# BatteryCharge.net
KiCad netlist of a schematic drawn in Altium Designer
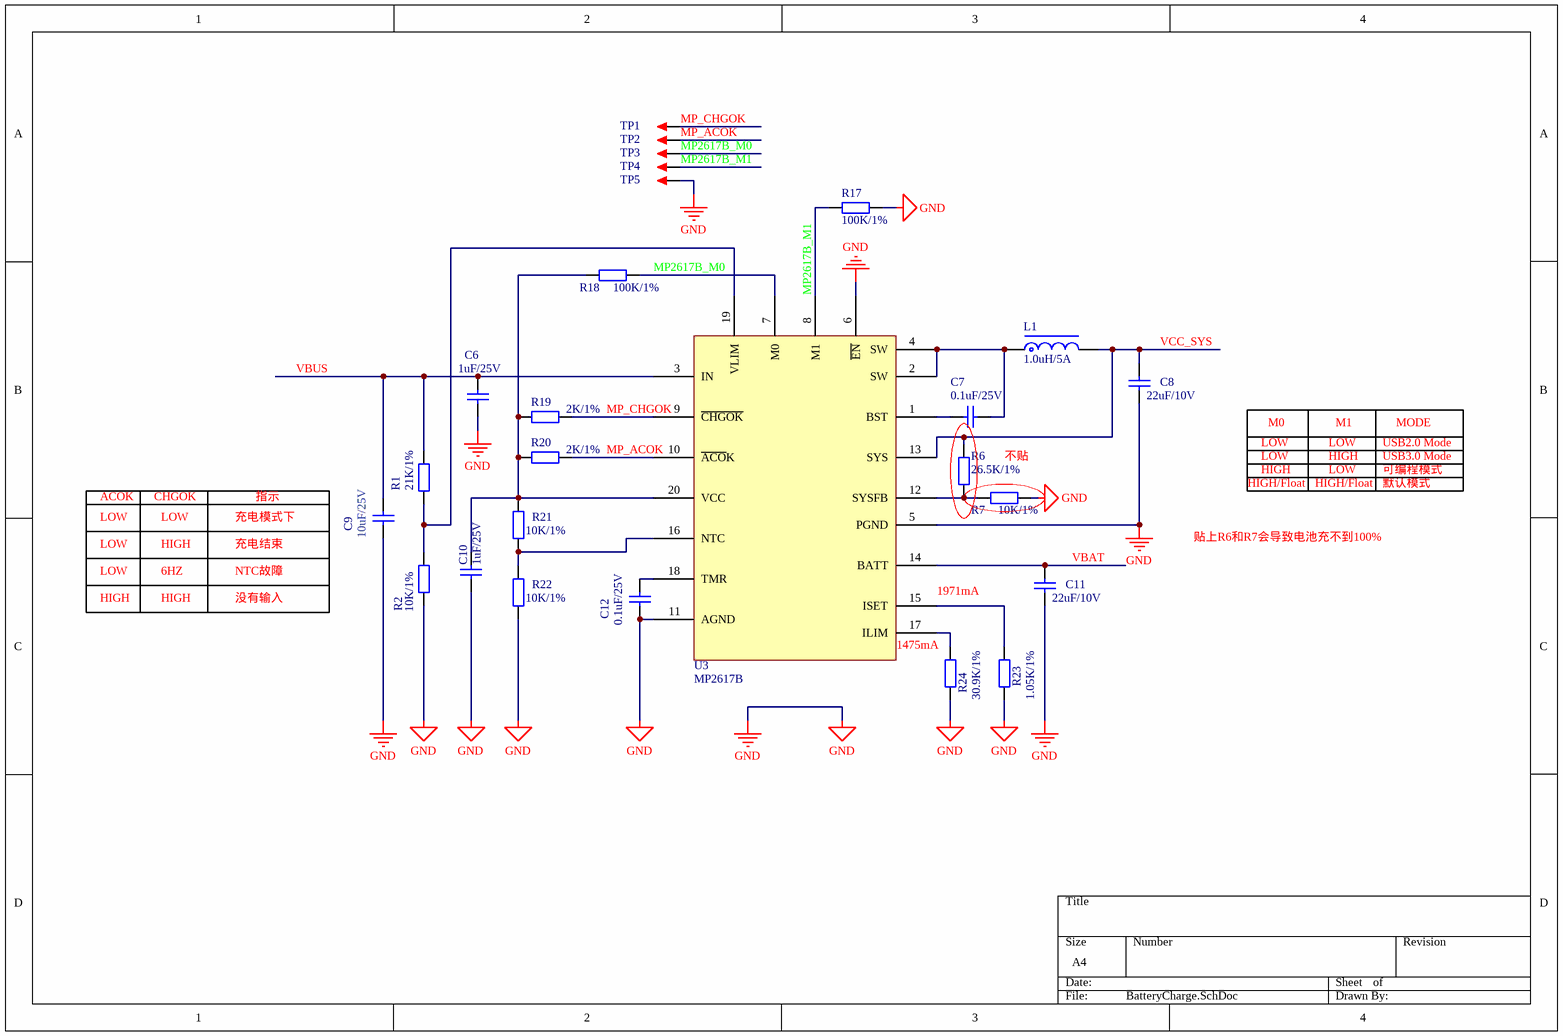
[diagram p0: BatteryCharge.SchDoc]

(export (version "E")
  (design (tool "Eeschema 10.0.6"))
  (components
    (comp (ref "C6")
      (value "1uF/25V")
      (footprint "C0402_L")
      (description "贴片电容")
      (libsource (lib "0.1 - 电阻-电容-电感-晶振-晶体-磁珠-电位器") (part "C"))
    )
    (comp (ref "C7")
      (value "0.1uF/25V")
      (footprint "C0402_L")
      (description "贴片电容")
      (libsource (lib "0.1 - 电阻-电容-电感-晶振-晶体-磁珠-电位器") (part "C"))
    )
    (comp (ref "C8")
      (value "22uF/10V")
      (footprint "C0603_L")
      (description "贴片电容")
      (libsource (lib "0.1 - 电阻-电容-电感-晶振-晶体-磁珠-电位器") (part "C"))
    )
    (comp (ref "C9")
      (value "10uF/25V")
      (footprint "C0603_L")
      (description "贴片电容")
      (libsource (lib "0.1 - 电阻-电容-电感-晶振-晶体-磁珠-电位器") (part "C"))
    )
    (comp (ref "C10")
      (value "1uF/25V")
      (footprint "C0402_L")
      (description "贴片电容")
      (libsource (lib "0.1 - 电阻-电容-电感-晶振-晶体-磁珠-电位器") (part "C"))
    )
    (comp (ref "C11")
      (value "22uF/10V")
      (footprint "C0603_L")
      (description "贴片电容")
      (libsource (lib "0.1 - 电阻-电容-电感-晶振-晶体-磁珠-电位器") (part "C"))
    )
    (comp (ref "C12")
      (value "0.1uF/25V")
      (footprint "C0402_L")
      (description "贴片电容")
      (libsource (lib "0.1 - 电阻-电容-电感-晶振-晶体-磁珠-电位器") (part "C"))
    )
    (comp (ref "L1")
      (value "1.0uH/5A")
      (footprint "L-SMD-0630")
      (description "CDRH功率屏蔽电感")
      (libsource (lib "0.1 - 电阻-电容-电感-晶振-晶体-磁珠-电位器") (part "L-CDRH"))
    )
    (comp (ref "R1")
      (value "21K/1%")
      (footprint "R0402_L")
      (description "贴片电阻")
      (libsource (lib "0.1 - 电阻-电容-电感-晶振-晶体-磁珠-电位器") (part "R"))
    )
    (comp (ref "R2")
      (value "10K/1%")
      (footprint "R0402_L")
      (description "贴片电阻")
      (libsource (lib "0.1 - 电阻-电容-电感-晶振-晶体-磁珠-电位器") (part "R"))
    )
    (comp (ref "R6")
      (value "26.5K/1%")
      (footprint "R0402_L")
      (description "贴片电阻")
      (libsource (lib "0.1 - 电阻-电容-电感-晶振-晶体-磁珠-电位器") (part "R"))
    )
    (comp (ref "R7")
      (value "10K/1%")
      (footprint "R0402_L")
      (description "贴片电阻")
      (libsource (lib "0.1 - 电阻-电容-电感-晶振-晶体-磁珠-电位器") (part "R"))
    )
    (comp (ref "R17")
      (value "100K/1%")
      (footprint "R0402_L")
      (description "贴片电阻")
      (libsource (lib "0.1 - 电阻-电容-电感-晶振-晶体-磁珠-电位器") (part "R"))
    )
    (comp (ref "R18")
      (value "100K/1%")
      (footprint "R0402_L")
      (description "贴片电阻")
      (libsource (lib "0.1 - 电阻-电容-电感-晶振-晶体-磁珠-电位器") (part "R"))
    )
    (comp (ref "R19")
      (value "2K/1%")
      (footprint "R0402_L")
      (description "贴片电阻")
      (libsource (lib "0.1 - 电阻-电容-电感-晶振-晶体-磁珠-电位器") (part "R"))
    )
    (comp (ref "R20")
      (value "2K/1%")
      (footprint "R0402_L")
      (description "贴片电阻")
      (libsource (lib "0.1 - 电阻-电容-电感-晶振-晶体-磁珠-电位器") (part "R"))
    )
    (comp (ref "R21")
      (value "10K/1%")
      (footprint "R0402_L")
      (description "贴片电阻")
      (libsource (lib "0.1 - 电阻-电容-电感-晶振-晶体-磁珠-电位器") (part "R"))
    )
    (comp (ref "R22")
      (value "10K/1%")
      (footprint "R0402_L")
      (description "贴片电阻")
      (libsource (lib "0.1 - 电阻-电容-电感-晶振-晶体-磁珠-电位器") (part "R"))
    )
    (comp (ref "R23")
      (value "1.05K/1%")
      (footprint "R0402_L")
      (description "贴片电阻")
      (libsource (lib "0.1 - 电阻-电容-电感-晶振-晶体-磁珠-电位器") (part "R"))
    )
    (comp (ref "R24")
      (value "30.9K/1%")
      (footprint "R0402_L")
      (description "贴片电阻")
      (libsource (lib "0.1 - 电阻-电容-电感-晶振-晶体-磁珠-电位器") (part "R"))
    )
    (comp (ref "TP1")
      (value "TEST")
      (footprint "TEST 1")
      (description "测试点")
      (libsource (lib "0.5 - 按键-开关-蜂鸣器-保险丝-电池-测试点-Mark点") (part "TEST"))
    )
    (comp (ref "TP2")
      (value "TEST")
      (footprint "TEST 1")
      (description "测试点")
      (libsource (lib "0.5 - 按键-开关-蜂鸣器-保险丝-电池-测试点-Mark点") (part "TEST"))
    )
    (comp (ref "TP3")
      (value "TEST")
      (footprint "TEST 1")
      (description "测试点")
      (libsource (lib "0.5 - 按键-开关-蜂鸣器-保险丝-电池-测试点-Mark点") (part "TEST"))
    )
    (comp (ref "TP4")
      (value "TEST")
      (footprint "TEST 1")
      (description "测试点")
      (libsource (lib "0.5 - 按键-开关-蜂鸣器-保险丝-电池-测试点-Mark点") (part "TEST"))
    )
    (comp (ref "TP5")
      (value "TEST")
      (footprint "TEST 1")
      (description "测试点")
      (libsource (lib "0.5 - 按键-开关-蜂鸣器-保险丝-电池-测试点-Mark点") (part "TEST"))
    )
    (comp (ref "U3")
      (value "MP2617B")
      (footprint "QFN-20")
      (description "锂电池充电IC，电源路径管理")
      (libsource (lib "lib") (part "MP2617B"))
    )
  )
  (nets
    (net (code "1") (name "/MP2617B_M0") (class "Default")
      (node (ref "R18") (pin "2") (pinfunction "2_2") (pintype "passive"))
      (node (ref "TP3") (pin "1") (pinfunction "1_1") (pintype "passive"))
      (node (ref "U3") (pin "7") (pinfunction "M0_7") (pintype "passive"))
    )
    (net (code "2") (name "/MP2617B_M1") (class "Default")
      (node (ref "R17") (pin "1") (pinfunction "1_1") (pintype "passive"))
      (node (ref "TP4") (pin "1") (pinfunction "1_1") (pintype "passive"))
      (node (ref "U3") (pin "8") (pinfunction "M1_8") (pintype "passive"))
    )
    (net (code "3") (name "/MP_ACOK") (class "Default")
      (node (ref "R20") (pin "2") (pinfunction "2_2") (pintype "passive"))
      (node (ref "TP2") (pin "1") (pinfunction "1_1") (pintype "passive"))
      (node (ref "U3") (pin "10") (pinfunction "~{ACO}K_10") (pintype "passive"))
    )
    (net (code "4") (name "/MP_CHGOK") (class "Default")
      (node (ref "R19") (pin "2") (pinfunction "2_2") (pintype "passive"))
      (node (ref "TP1") (pin "1") (pinfunction "1_1") (pintype "passive"))
      (node (ref "U3") (pin "9") (pinfunction "~{CHGOK}_9") (pintype "passive"))
    )
    (net (code "5") (name "/VBAT") (class "Default")
      (node (ref "C11") (pin "2") (pinfunction "2_2") (pintype "passive"))
      (node (ref "U3") (pin "14") (pinfunction "BATT_14") (pintype "passive"))
    )
    (net (code "6") (name "/VBUS") (class "Default")
      (node (ref "C6") (pin "2") (pinfunction "2_2") (pintype "passive"))
      (node (ref "C9") (pin "2") (pinfunction "2_2") (pintype "passive"))
      (node (ref "R1") (pin "2") (pinfunction "2_2") (pintype "passive"))
      (node (ref "U3") (pin "3") (pinfunction "IN_3") (pintype "passive"))
    )
    (net (code "7") (name "/VCC_SYS") (class "Default")
      (node (ref "C8") (pin "2") (pinfunction "2_2") (pintype "passive"))
      (node (ref "L1") (pin "2") (pinfunction "2_2") (pintype "passive"))
      (node (ref "R6") (pin "2") (pinfunction "2_2") (pintype "passive"))
      (node (ref "U3") (pin "13") (pinfunction "SYS_13") (pintype "passive"))
    )
    (net (code "8") (name "GND") (class "Default")
      (node (ref "C10") (pin "1") (pinfunction "1_1") (pintype "passive"))
      (node (ref "C11") (pin "1") (pinfunction "1_1") (pintype "passive"))
      (node (ref "C12") (pin "2") (pinfunction "2_2") (pintype "passive"))
      (node (ref "C6") (pin "1") (pinfunction "1_1") (pintype "passive"))
      (node (ref "C8") (pin "1") (pinfunction "1_1") (pintype "passive"))
      (node (ref "C9") (pin "1") (pinfunction "1_1") (pintype "passive"))
      (node (ref "R17") (pin "2") (pinfunction "2_2") (pintype "passive"))
      (node (ref "R2") (pin "1") (pinfunction "1_1") (pintype "passive"))
      (node (ref "R22") (pin "1") (pinfunction "1_1") (pintype "passive"))
      (node (ref "R23") (pin "1") (pinfunction "1_1") (pintype "passive"))
      (node (ref "R24") (pin "1") (pinfunction "1_1") (pintype "passive"))
      (node (ref "R7") (pin "2") (pinfunction "2_2") (pintype "passive"))
      (node (ref "TP5") (pin "1") (pinfunction "1_1") (pintype "passive"))
      (node (ref "U3") (pin "11") (pinfunction "AGND_11") (pintype "passive"))
      (node (ref "U3") (pin "5") (pinfunction "PGND_5") (pintype "passive"))
      (node (ref "U3") (pin "6") (pinfunction "~{EN}_6") (pintype "passive"))
    )
    (net (code "9") (name "Net-(C7-Pad1)") (class "Default")
      (node (ref "C7") (pin "1") (pinfunction "1_1") (pintype "passive"))
      (node (ref "L1") (pin "1") (pinfunction "1_1") (pintype "passive"))
      (node (ref "U3") (pin "2") (pinfunction "SW_2") (pintype "passive"))
      (node (ref "U3") (pin "4") (pinfunction "SW_4") (pintype "passive"))
    )
    (net (code "10") (name "Net-(U3-BST)") (class "Default")
      (node (ref "C7") (pin "2") (pinfunction "2_2") (pintype "passive"))
      (node (ref "U3") (pin "1") (pinfunction "BST_1") (pintype "passive"))
    )
    (net (code "11") (name "Net-(U3-ILIM)") (class "Default")
      (node (ref "R24") (pin "2") (pinfunction "2_2") (pintype "passive"))
      (node (ref "U3") (pin "17") (pinfunction "ILIM_17") (pintype "passive"))
    )
    (net (code "12") (name "Net-(U3-ISET)") (class "Default")
      (node (ref "R23") (pin "2") (pinfunction "2_2") (pintype "passive"))
      (node (ref "U3") (pin "15") (pinfunction "ISET_15") (pintype "passive"))
    )
    (net (code "13") (name "Net-(U3-NTC)") (class "Default")
      (node (ref "R21") (pin "1") (pinfunction "1_1") (pintype "passive"))
      (node (ref "R22") (pin "2") (pinfunction "2_2") (pintype "passive"))
      (node (ref "U3") (pin "16") (pinfunction "NTC_16") (pintype "passive"))
    )
    (net (code "14") (name "Net-(U3-SYSFB)") (class "Default")
      (node (ref "R6") (pin "1") (pinfunction "1_1") (pintype "passive"))
      (node (ref "R7") (pin "1") (pinfunction "1_1") (pintype "passive"))
      (node (ref "U3") (pin "12") (pinfunction "SYSFB_12") (pintype "passive"))
    )
    (net (code "15") (name "Net-(U3-TMR)") (class "Default")
      (node (ref "C12") (pin "1") (pinfunction "1_1") (pintype "passive"))
      (node (ref "U3") (pin "18") (pinfunction "TMR_18") (pintype "passive"))
    )
    (net (code "16") (name "Net-(U3-VCC)") (class "Default")
      (node (ref "C10") (pin "2") (pinfunction "2_2") (pintype "passive"))
      (node (ref "R18") (pin "1") (pinfunction "1_1") (pintype "passive"))
      (node (ref "R19") (pin "1") (pinfunction "1_1") (pintype "passive"))
      (node (ref "R20") (pin "1") (pinfunction "1_1") (pintype "passive"))
      (node (ref "R21") (pin "2") (pinfunction "2_2") (pintype "passive"))
      (node (ref "U3") (pin "20") (pinfunction "VCC_20") (pintype "passive"))
    )
    (net (code "17") (name "Net-(U3-VLIM)") (class "Default")
      (node (ref "R1") (pin "1") (pinfunction "1_1") (pintype "passive"))
      (node (ref "R2") (pin "2") (pinfunction "2_2") (pintype "passive"))
      (node (ref "U3") (pin "19") (pinfunction "VLIM_19") (pintype "passive"))
    )
  )
)
